# PCB.net
KiCad netlist of a schematic drawn in EAGLE
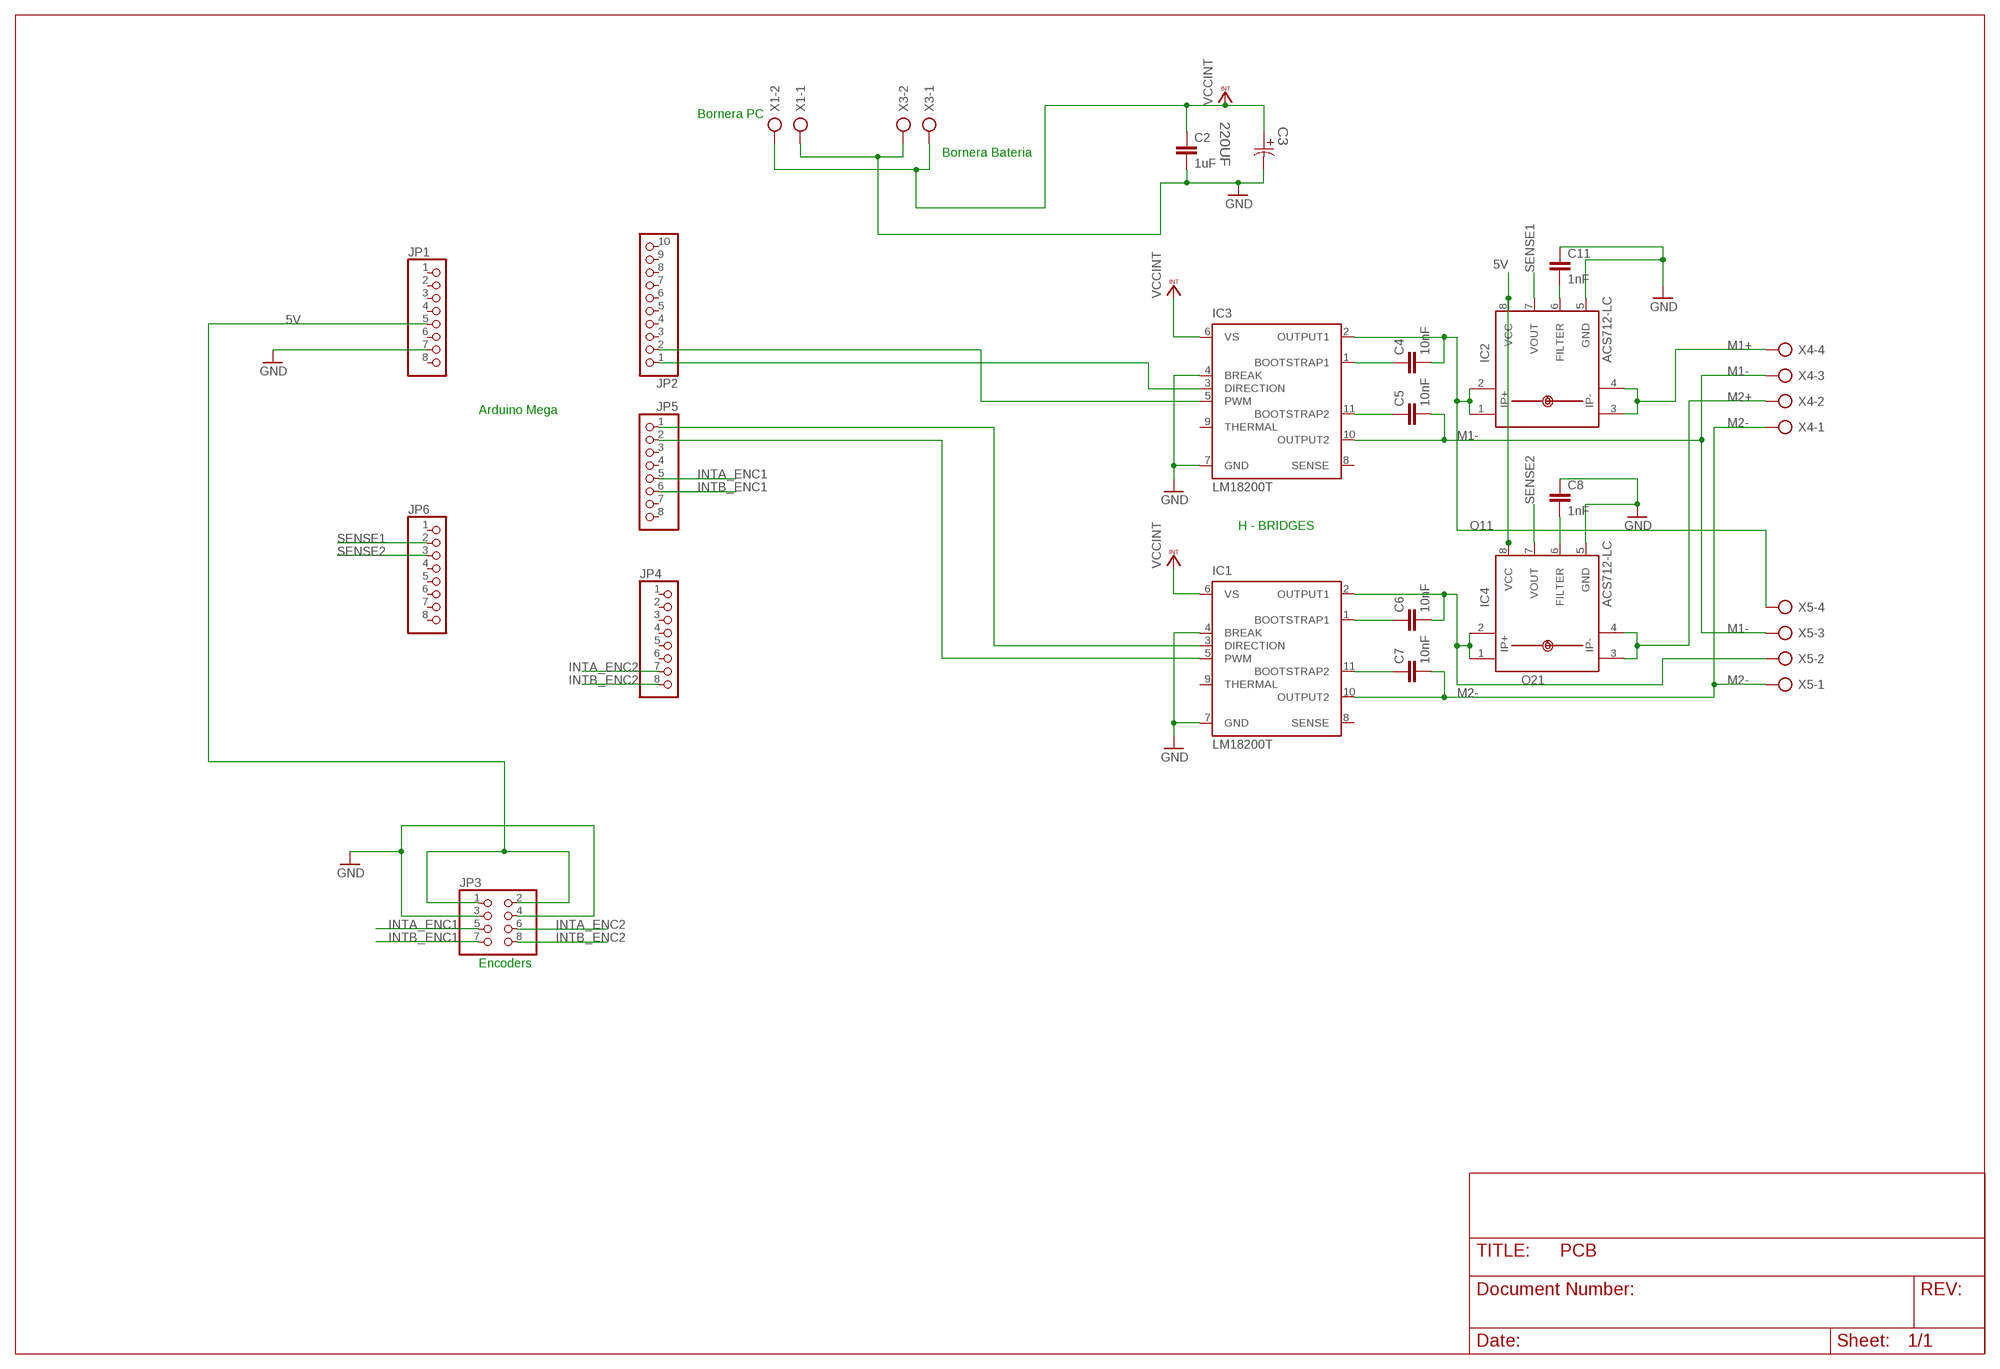
[diagram p0: schematic, sheet 1]

(export (version "E")
  (design (tool "Eeschema 10.0.6"))
  (components
    (comp (ref "C2")
      (value "1uF")
      (footprint "eagle-import:C050-030X075")
      (libsource (lib "eagle-import") (part "C-EU050-030X075"))
    )
    (comp (ref "C3")
      (value "220UF")
      (footprint "eagle-import:CAPPR500-1000X3200")
      (fields (field (name "MPN") "EEUFM1H221") (field (name "TOLERANCE") "±20 %"))
      (libsource (lib "eagle-import") (part "EEU-P5.0-D10FM1H221"))
    )
    (comp (ref "C4")
      (value "10nF")
      (footprint "eagle-import:C050-030X075")
      (libsource (lib "eagle-import") (part "C-EU050-030X075"))
    )
    (comp (ref "C5")
      (value "10nF")
      (footprint "eagle-import:C050-030X075")
      (libsource (lib "eagle-import") (part "C-EU050-030X075"))
    )
    (comp (ref "C6")
      (value "10nF")
      (footprint "eagle-import:C050-030X075")
      (libsource (lib "eagle-import") (part "C-EU050-030X075"))
    )
    (comp (ref "C7")
      (value "10nF")
      (footprint "eagle-import:C050-030X075")
      (libsource (lib "eagle-import") (part "C-EU050-030X075"))
    )
    (comp (ref "C8")
      (value "1nF")
      (footprint "eagle-import:C050-030X075")
      (libsource (lib "eagle-import") (part "C-EU050-030X075"))
    )
    (comp (ref "C11")
      (value "1nF")
      (footprint "eagle-import:C050-030X075")
      (libsource (lib "eagle-import") (part "C-EU050-030X075"))
    )
    (comp (ref "IC1")
      (value "LM18200T")
      (footprint "eagle-import:TO-220-11")
      (libsource (lib "eagle-import") (part "LM18200T"))
    )
    (comp (ref "IC2")
      (value "ACS712-LC")
      (footprint "eagle-import:SOIC8")
      (libsource (lib "eagle-import") (part "ACS712-LC"))
    )
    (comp (ref "IC3")
      (value "LM18200T")
      (footprint "eagle-import:TO-220-11")
      (libsource (lib "eagle-import") (part "LM18200T"))
    )
    (comp (ref "IC4")
      (value "ACS712-LC")
      (footprint "eagle-import:SOIC8")
      (libsource (lib "eagle-import") (part "ACS712-LC"))
    )
    (comp (ref "JP1")
      (value "PINHD-1X8")
      (footprint "eagle-import:1X08")
      (libsource (lib "eagle-import") (part "PINHD-1X8"))
    )
    (comp (ref "JP2")
      (value "PINHD-1X10")
      (footprint "eagle-import:1X10")
      (libsource (lib "eagle-import") (part "PINHD-1X10"))
    )
    (comp (ref "JP3")
      (value "PINHD-2X4")
      (footprint "eagle-import:2X04")
      (libsource (lib "eagle-import") (part "PINHD-2X4"))
    )
    (comp (ref "JP4")
      (value "PINHD-1X8")
      (footprint "eagle-import:1X08")
      (libsource (lib "eagle-import") (part "PINHD-1X8"))
    )
    (comp (ref "JP5")
      (value "PINHD-1X8")
      (footprint "eagle-import:1X08")
      (libsource (lib "eagle-import") (part "PINHD-1X8"))
    )
    (comp (ref "JP6")
      (value "PINHD-1X8")
      (footprint "eagle-import:1X08")
      (libsource (lib "eagle-import") (part "PINHD-1X8"))
    )
    (comp (ref "X1")
      (value "AK500/2")
      (footprint "eagle-import:AK500_2")
      (libsource (lib "eagle-import") (part "AK500/2"))
    )
    (comp (ref "X3")
      (value "AK500/2")
      (footprint "eagle-import:AK500_2")
      (libsource (lib "eagle-import") (part "AK500/2"))
    )
    (comp (ref "X4")
      (value "AK500/4-H")
      (footprint "eagle-import:AK500_4-H")
      (libsource (lib "eagle-import") (part "AK500/4-H"))
    )
    (comp (ref "X5")
      (value "AK500/4-H")
      (footprint "eagle-import:AK500_4-H")
      (libsource (lib "eagle-import") (part "AK500/4-H"))
    )
  )
  (nets
    (net (code "1") (name "/5V") (class "Default")
      (node (ref "IC2") (pin "8") (pinfunction "VCC_8") (pintype "power_in"))
      (node (ref "IC4") (pin "8") (pinfunction "VCC_8") (pintype "power_in"))
      (node (ref "JP1") (pin "5") (pinfunction "5_5") (pintype "passive"))
      (node (ref "JP3") (pin "1") (pinfunction "1_1") (pintype "passive"))
      (node (ref "JP3") (pin "2") (pinfunction "2_2") (pintype "passive"))
    )
    (net (code "2") (name "/INTA_ENC1") (class "Default")
      (node (ref "JP3") (pin "5") (pinfunction "5_5") (pintype "passive"))
      (node (ref "JP5") (pin "5") (pinfunction "5_5") (pintype "passive"))
    )
    (net (code "3") (name "/INTA_ENC2") (class "Default")
      (node (ref "JP3") (pin "6") (pinfunction "6_6") (pintype "passive"))
      (node (ref "JP4") (pin "7") (pinfunction "7_7") (pintype "passive"))
    )
    (net (code "4") (name "/INTB_ENC1") (class "Default")
      (node (ref "JP3") (pin "7") (pinfunction "7_7") (pintype "passive"))
      (node (ref "JP5") (pin "6") (pinfunction "6_6") (pintype "passive"))
    )
    (net (code "5") (name "/INTB_ENC2") (class "Default")
      (node (ref "JP3") (pin "8") (pinfunction "8_8") (pintype "passive"))
      (node (ref "JP4") (pin "8") (pinfunction "8_8") (pintype "passive"))
    )
    (net (code "6") (name "/M1+") (class "Default")
      (node (ref "IC2") (pin "3") (pinfunction "IP-_3") (pintype "passive"))
      (node (ref "IC2") (pin "4") (pinfunction "IP-1_4") (pintype "passive"))
      (node (ref "X4") (pin "4") (pinfunction "KL_4") (pintype "passive"))
    )
    (net (code "7") (name "/M1-") (class "Default")
      (node (ref "C5") (pin "2") (pinfunction "2_2") (pintype "passive"))
      (node (ref "IC3") (pin "10") (pinfunction "OUTPUT2_10") (pintype "output"))
      (node (ref "X4") (pin "3") (pinfunction "KL_3") (pintype "passive"))
      (node (ref "X5") (pin "3") (pinfunction "KL_3") (pintype "passive"))
    )
    (net (code "8") (name "/M2+") (class "Default")
      (node (ref "IC4") (pin "3") (pinfunction "IP-_3") (pintype "passive"))
      (node (ref "IC4") (pin "4") (pinfunction "IP-1_4") (pintype "passive"))
      (node (ref "X4") (pin "2") (pinfunction "KL_2") (pintype "passive"))
    )
    (net (code "9") (name "/M2-") (class "Default")
      (node (ref "C7") (pin "2") (pinfunction "2_2") (pintype "passive"))
      (node (ref "IC1") (pin "10") (pinfunction "OUTPUT2_10") (pintype "output"))
      (node (ref "X4") (pin "1") (pinfunction "KL_1") (pintype "passive"))
      (node (ref "X5") (pin "1") (pinfunction "KL_1") (pintype "passive"))
    )
    (net (code "10") (name "/O11") (class "Default")
      (node (ref "C4") (pin "2") (pinfunction "2_2") (pintype "passive"))
      (node (ref "IC2") (pin "1") (pinfunction "IP+_1") (pintype "passive"))
      (node (ref "IC2") (pin "2") (pinfunction "IP+1_2") (pintype "passive"))
      (node (ref "IC3") (pin "2") (pinfunction "OUTPUT1_2") (pintype "output"))
      (node (ref "X5") (pin "4") (pinfunction "KL_4") (pintype "passive"))
    )
    (net (code "11") (name "/O21") (class "Default")
      (node (ref "C6") (pin "2") (pinfunction "2_2") (pintype "passive"))
      (node (ref "IC1") (pin "2") (pinfunction "OUTPUT1_2") (pintype "output"))
      (node (ref "IC4") (pin "1") (pinfunction "IP+_1") (pintype "passive"))
      (node (ref "IC4") (pin "2") (pinfunction "IP+1_2") (pintype "passive"))
      (node (ref "X5") (pin "2") (pinfunction "KL_2") (pintype "passive"))
    )
    (net (code "12") (name "/SENSE1") (class "Default")
      (node (ref "IC2") (pin "7") (pinfunction "VOUT_7") (pintype "output"))
      (node (ref "JP6") (pin "2") (pinfunction "2_2") (pintype "passive"))
    )
    (net (code "13") (name "/SENSE2") (class "Default")
      (node (ref "IC4") (pin "7") (pinfunction "VOUT_7") (pintype "output"))
      (node (ref "JP6") (pin "3") (pinfunction "3_3") (pintype "passive"))
    )
    (net (code "14") (name "GND") (class "Default")
      (node (ref "C11") (pin "1") (pinfunction "1_1") (pintype "passive"))
      (node (ref "C2") (pin "2") (pinfunction "2_2") (pintype "passive"))
      (node (ref "C3") (pin "2") (pinfunction "2_2") (pintype "passive"))
      (node (ref "C8") (pin "1") (pinfunction "1_1") (pintype "passive"))
      (node (ref "IC1") (pin "4") (pinfunction "BREAK_4") (pintype "input"))
      (node (ref "IC1") (pin "7") (pinfunction "GND_7") (pintype "power_in"))
      (node (ref "IC2") (pin "5") (pinfunction "GND_5") (pintype "power_in"))
      (node (ref "IC3") (pin "4") (pinfunction "BREAK_4") (pintype "input"))
      (node (ref "IC3") (pin "7") (pinfunction "GND_7") (pintype "power_in"))
      (node (ref "IC4") (pin "5") (pinfunction "GND_5") (pintype "power_in"))
      (node (ref "JP1") (pin "7") (pinfunction "7_7") (pintype "passive"))
      (node (ref "JP3") (pin "3") (pinfunction "3_3") (pintype "passive"))
      (node (ref "JP3") (pin "4") (pinfunction "4_4") (pintype "passive"))
      (node (ref "X1") (pin "1") (pinfunction "KL_1") (pintype "passive"))
      (node (ref "X3") (pin "2") (pinfunction "KL_2") (pintype "passive"))
    )
    (net (code "15") (name "Net-(IC1-BOOTSTRAP1)") (class "Default")
      (node (ref "C6") (pin "1") (pinfunction "1_1") (pintype "passive"))
      (node (ref "IC1") (pin "1") (pinfunction "BOOTSTRAP1_1") (pintype "input"))
    )
    (net (code "16") (name "Net-(IC1-BOOTSTRAP2)") (class "Default")
      (node (ref "C7") (pin "1") (pinfunction "1_1") (pintype "passive"))
      (node (ref "IC1") (pin "11") (pinfunction "BOOTSTRAP2_11") (pintype "input"))
    )
    (net (code "17") (name "Net-(IC1-DIRECTION)") (class "Default")
      (node (ref "IC1") (pin "3") (pinfunction "DIRECTION_3") (pintype "input"))
      (node (ref "JP5") (pin "1") (pinfunction "1_1") (pintype "passive"))
    )
    (net (code "18") (name "Net-(IC1-PWM)") (class "Default")
      (node (ref "IC1") (pin "5") (pinfunction "PWM_5") (pintype "input"))
      (node (ref "JP5") (pin "2") (pinfunction "2_2") (pintype "passive"))
    )
    (net (code "19") (name "Net-(IC2-FILTER)") (class "Default")
      (node (ref "C11") (pin "2") (pinfunction "2_2") (pintype "passive"))
      (node (ref "IC2") (pin "6") (pinfunction "FILTER_6") (pintype "bidirectional"))
    )
    (net (code "20") (name "Net-(IC3-BOOTSTRAP1)") (class "Default")
      (node (ref "C4") (pin "1") (pinfunction "1_1") (pintype "passive"))
      (node (ref "IC3") (pin "1") (pinfunction "BOOTSTRAP1_1") (pintype "input"))
    )
    (net (code "21") (name "Net-(IC3-BOOTSTRAP2)") (class "Default")
      (node (ref "C5") (pin "1") (pinfunction "1_1") (pintype "passive"))
      (node (ref "IC3") (pin "11") (pinfunction "BOOTSTRAP2_11") (pintype "input"))
    )
    (net (code "22") (name "Net-(IC3-DIRECTION)") (class "Default")
      (node (ref "IC3") (pin "3") (pinfunction "DIRECTION_3") (pintype "input"))
      (node (ref "JP2") (pin "1") (pinfunction "1_1") (pintype "passive"))
    )
    (net (code "23") (name "Net-(IC3-PWM)") (class "Default")
      (node (ref "IC3") (pin "5") (pinfunction "PWM_5") (pintype "input"))
      (node (ref "JP2") (pin "2") (pinfunction "2_2") (pintype "passive"))
    )
    (net (code "24") (name "Net-(IC4-FILTER)") (class "Default")
      (node (ref "C8") (pin "2") (pinfunction "2_2") (pintype "passive"))
      (node (ref "IC4") (pin "6") (pinfunction "FILTER_6") (pintype "bidirectional"))
    )
    (net (code "25") (name "VCCINT") (class "Default")
      (node (ref "C2") (pin "1") (pinfunction "1_1") (pintype "passive"))
      (node (ref "C3") (pin "1") (pinfunction "1_1") (pintype "passive"))
      (node (ref "IC1") (pin "6") (pinfunction "VS_6") (pintype "power_in"))
      (node (ref "IC3") (pin "6") (pinfunction "VS_6") (pintype "power_in"))
      (node (ref "X1") (pin "2") (pinfunction "KL_2") (pintype "passive"))
      (node (ref "X3") (pin "1") (pinfunction "KL_1") (pintype "passive"))
    )
    (net (code "26") (name "unconnected-(IC1-SENSE-Pad8)") (class "Default")
      (node (ref "IC1") (pin "8") (pinfunction "SENSE_8") (pintype "output"))
    )
    (net (code "27") (name "unconnected-(IC1-THERMAL-Pad9)") (class "Default")
      (node (ref "IC1") (pin "9") (pinfunction "THERMAL_9") (pintype "output"))
    )
    (net (code "28") (name "unconnected-(IC3-SENSE-Pad8)") (class "Default")
      (node (ref "IC3") (pin "8") (pinfunction "SENSE_8") (pintype "output"))
    )
    (net (code "29") (name "unconnected-(IC3-THERMAL-Pad9)") (class "Default")
      (node (ref "IC3") (pin "9") (pinfunction "THERMAL_9") (pintype "output"))
    )
    (net (code "30") (name "unconnected-(JP1-Pad1)") (class "Default")
      (node (ref "JP1") (pin "1") (pinfunction "1_1") (pintype "passive"))
    )
    (net (code "31") (name "unconnected-(JP1-Pad2)") (class "Default")
      (node (ref "JP1") (pin "2") (pinfunction "2_2") (pintype "passive"))
    )
    (net (code "32") (name "unconnected-(JP1-Pad3)") (class "Default")
      (node (ref "JP1") (pin "3") (pinfunction "3_3") (pintype "passive"))
    )
    (net (code "33") (name "unconnected-(JP1-Pad4)") (class "Default")
      (node (ref "JP1") (pin "4") (pinfunction "4_4") (pintype "passive"))
    )
    (net (code "34") (name "unconnected-(JP1-Pad6)") (class "Default")
      (node (ref "JP1") (pin "6") (pinfunction "6_6") (pintype "passive"))
    )
    (net (code "35") (name "unconnected-(JP1-Pad8)") (class "Default")
      (node (ref "JP1") (pin "8") (pinfunction "8_8") (pintype "passive"))
    )
    (net (code "36") (name "unconnected-(JP2-Pad3)") (class "Default")
      (node (ref "JP2") (pin "3") (pinfunction "3_3") (pintype "passive"))
    )
    (net (code "37") (name "unconnected-(JP2-Pad4)") (class "Default")
      (node (ref "JP2") (pin "4") (pinfunction "4_4") (pintype "passive"))
    )
    (net (code "38") (name "unconnected-(JP2-Pad5)") (class "Default")
      (node (ref "JP2") (pin "5") (pinfunction "5_5") (pintype "passive"))
    )
    (net (code "39") (name "unconnected-(JP2-Pad6)") (class "Default")
      (node (ref "JP2") (pin "6") (pinfunction "6_6") (pintype "passive"))
    )
    (net (code "40") (name "unconnected-(JP2-Pad7)") (class "Default")
      (node (ref "JP2") (pin "7") (pinfunction "7_7") (pintype "passive"))
    )
    (net (code "41") (name "unconnected-(JP2-Pad8)") (class "Default")
      (node (ref "JP2") (pin "8") (pinfunction "8_8") (pintype "passive"))
    )
    (net (code "42") (name "unconnected-(JP2-Pad9)") (class "Default")
      (node (ref "JP2") (pin "9") (pinfunction "9_9") (pintype "passive"))
    )
    (net (code "43") (name "unconnected-(JP2-Pad10)") (class "Default")
      (node (ref "JP2") (pin "10") (pinfunction "10_10") (pintype "passive"))
    )
    (net (code "44") (name "unconnected-(JP4-Pad1)") (class "Default")
      (node (ref "JP4") (pin "1") (pinfunction "1_1") (pintype "passive"))
    )
    (net (code "45") (name "unconnected-(JP4-Pad2)") (class "Default")
      (node (ref "JP4") (pin "2") (pinfunction "2_2") (pintype "passive"))
    )
    (net (code "46") (name "unconnected-(JP4-Pad3)") (class "Default")
      (node (ref "JP4") (pin "3") (pinfunction "3_3") (pintype "passive"))
    )
    (net (code "47") (name "unconnected-(JP4-Pad4)") (class "Default")
      (node (ref "JP4") (pin "4") (pinfunction "4_4") (pintype "passive"))
    )
    (net (code "48") (name "unconnected-(JP4-Pad5)") (class "Default")
      (node (ref "JP4") (pin "5") (pinfunction "5_5") (pintype "passive"))
    )
    (net (code "49") (name "unconnected-(JP4-Pad6)") (class "Default")
      (node (ref "JP4") (pin "6") (pinfunction "6_6") (pintype "passive"))
    )
    (net (code "50") (name "unconnected-(JP5-Pad3)") (class "Default")
      (node (ref "JP5") (pin "3") (pinfunction "3_3") (pintype "passive"))
    )
    (net (code "51") (name "unconnected-(JP5-Pad4)") (class "Default")
      (node (ref "JP5") (pin "4") (pinfunction "4_4") (pintype "passive"))
    )
    (net (code "52") (name "unconnected-(JP5-Pad7)") (class "Default")
      (node (ref "JP5") (pin "7") (pinfunction "7_7") (pintype "passive"))
    )
    (net (code "53") (name "unconnected-(JP5-Pad8)") (class "Default")
      (node (ref "JP5") (pin "8") (pinfunction "8_8") (pintype "passive"))
    )
    (net (code "54") (name "unconnected-(JP6-Pad1)") (class "Default")
      (node (ref "JP6") (pin "1") (pinfunction "1_1") (pintype "passive"))
    )
    (net (code "55") (name "unconnected-(JP6-Pad4)") (class "Default")
      (node (ref "JP6") (pin "4") (pinfunction "4_4") (pintype "passive"))
    )
    (net (code "56") (name "unconnected-(JP6-Pad5)") (class "Default")
      (node (ref "JP6") (pin "5") (pinfunction "5_5") (pintype "passive"))
    )
    (net (code "57") (name "unconnected-(JP6-Pad6)") (class "Default")
      (node (ref "JP6") (pin "6") (pinfunction "6_6") (pintype "passive"))
    )
    (net (code "58") (name "unconnected-(JP6-Pad7)") (class "Default")
      (node (ref "JP6") (pin "7") (pinfunction "7_7") (pintype "passive"))
    )
    (net (code "59") (name "unconnected-(JP6-Pad8)") (class "Default")
      (node (ref "JP6") (pin "8") (pinfunction "8_8") (pintype "passive"))
    )
  )
)
